# 4_cpu.net
KiCad netlist of a schematic drawn in Altium Designer
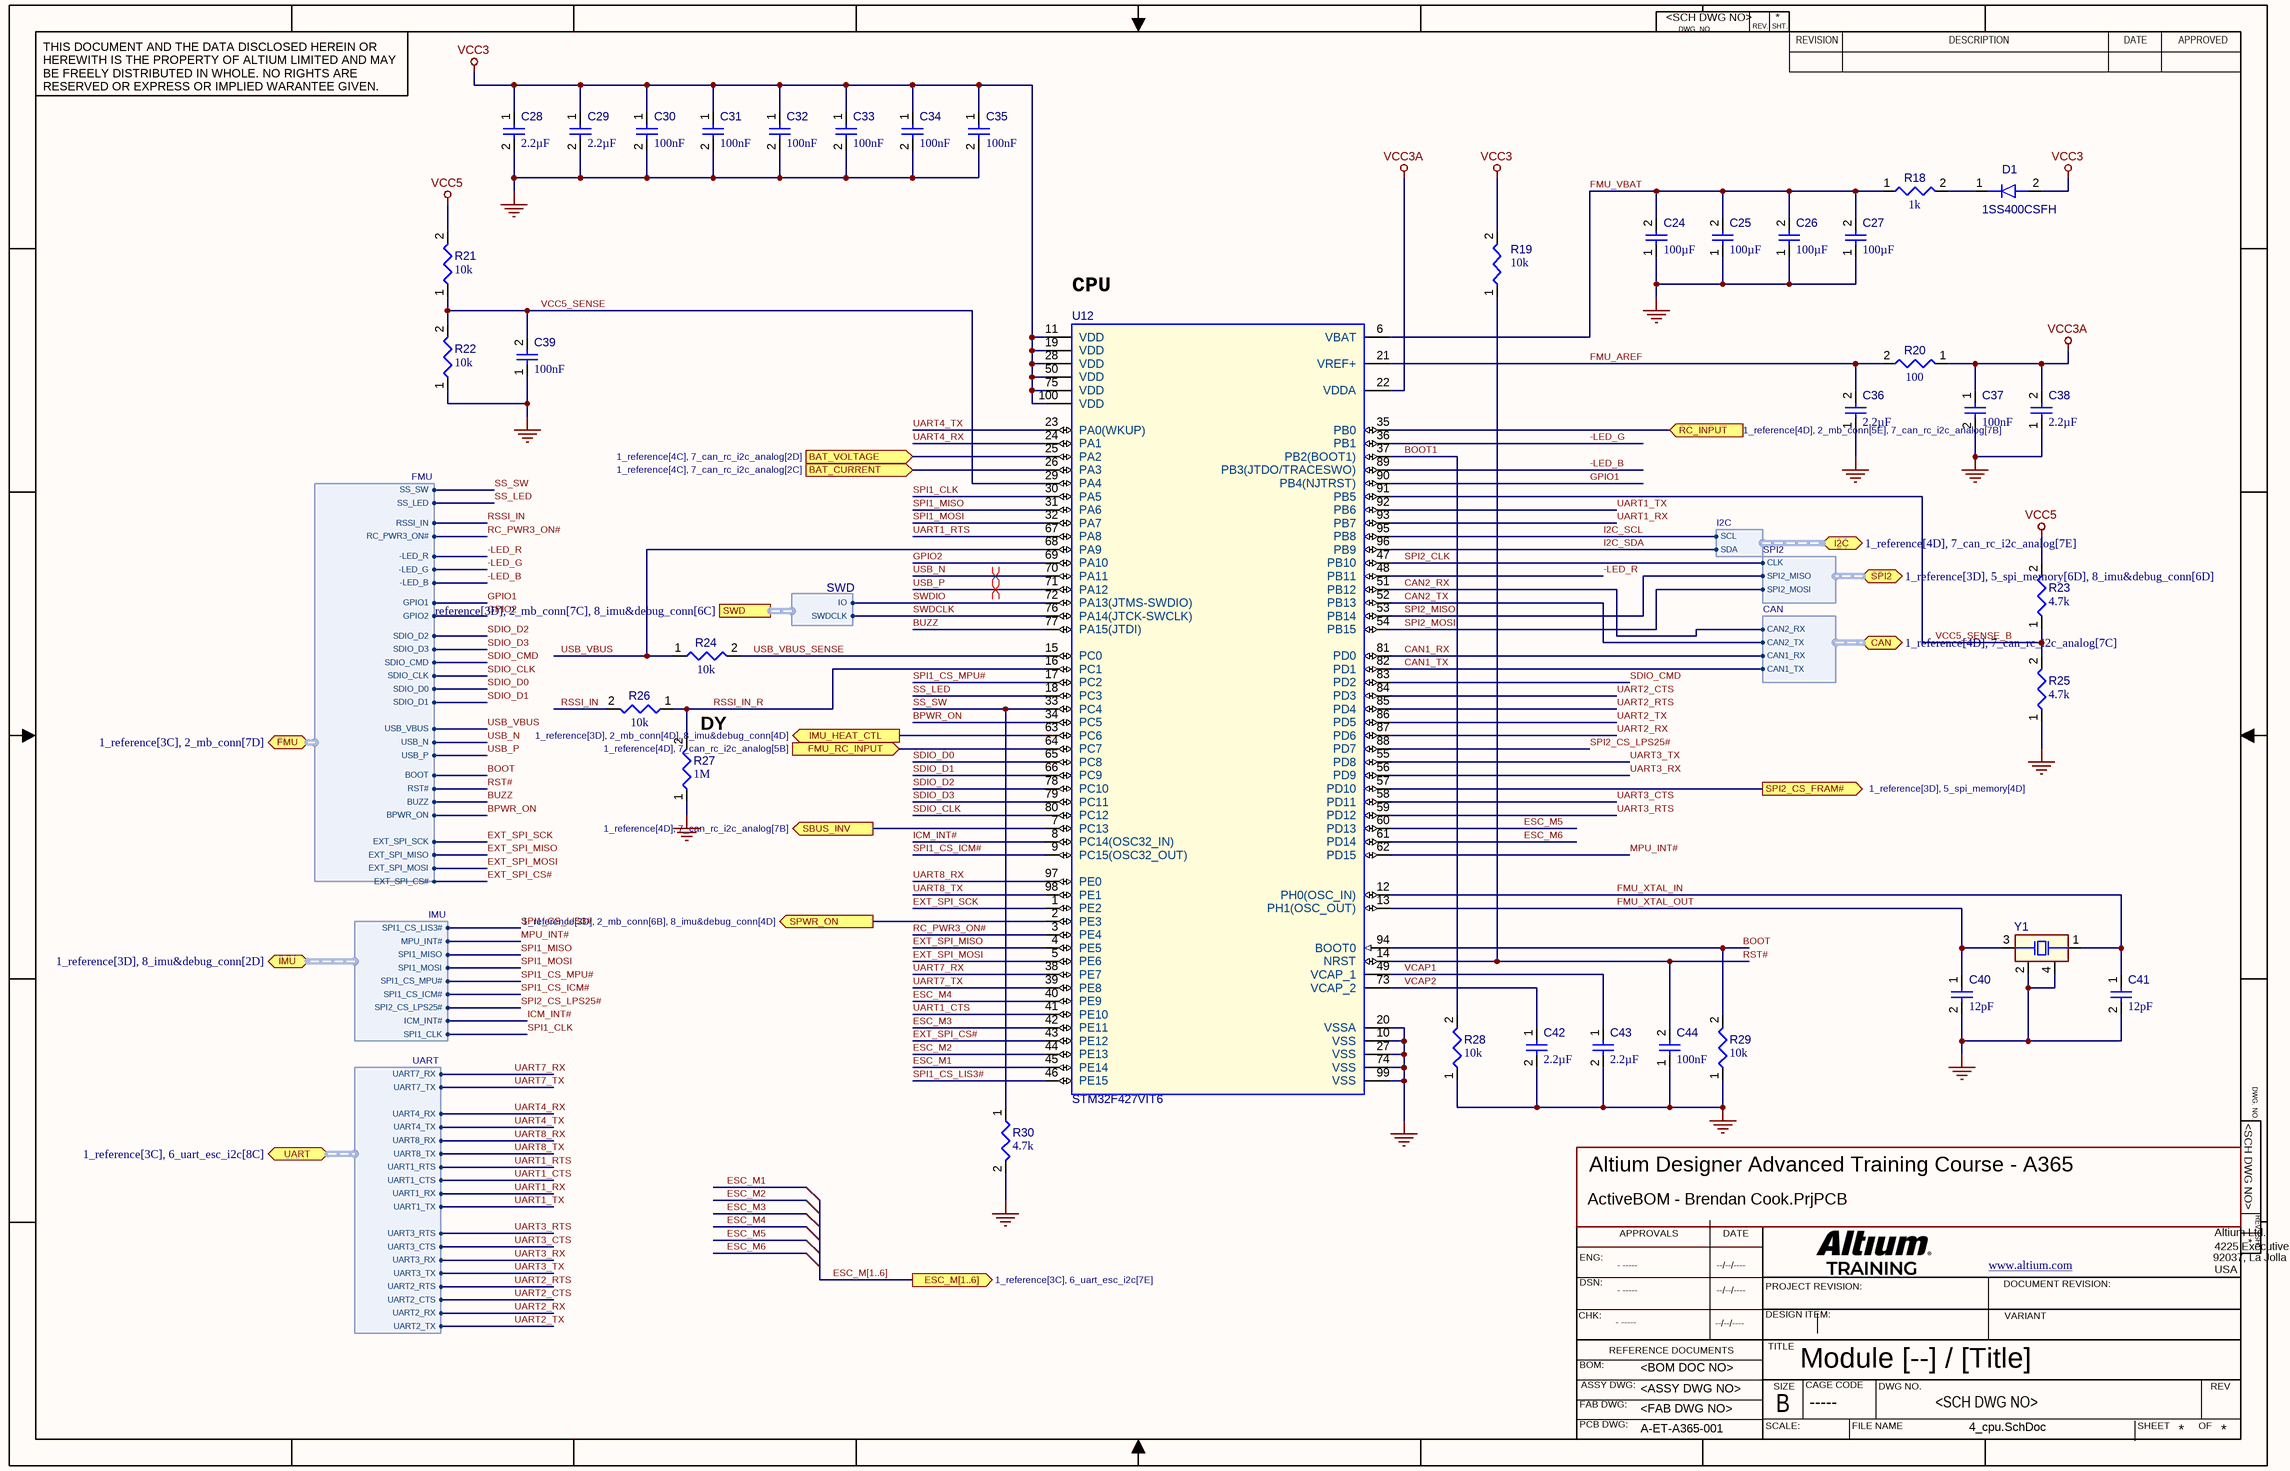
[diagram p0: 4_cpu.SchDoc]

(export (version "E")
  (design (tool "Eeschema 10.0.6"))
  (components
    (comp (ref "C24")
      (value "100µF")
      (footprint "CAPC0805(2012)145_L")
      (description "Chip Capacitor, 100µF +/-20%, 6.3V, 0805, Thickness 1.45 mm")
      (fields (field (name "TOLERANCE") "10%") (field (name "Comment") "Capacitor 100µF +/-20% 6.3V 0805"))
      (libsource (lib "MHH -  Altium Advanced Course A365 01") (part "CAP-NP-2"))
    )
    (comp (ref "C25")
      (value "100µF")
      (footprint "CAPC0805(2012)145_L")
      (description "Chip Capacitor, 100µF +/-20%, 6.3V, 0805, Thickness 1.45 mm")
      (fields (field (name "TOLERANCE") "10%") (field (name "Comment") "Capacitor 100µF +/-20% 6.3V 0805"))
      (libsource (lib "MHH -  Altium Advanced Course A365 01") (part "CAP-NP-2"))
    )
    (comp (ref "C26")
      (value "100µF")
      (footprint "CAPC0805(2012)145_L")
      (description "Chip Capacitor, 100µF +/-20%, 6.3V, 0805, Thickness 1.45 mm")
      (fields (field (name "TOLERANCE") "10%") (field (name "Comment") "Capacitor 100µF +/-20% 6.3V 0805"))
      (libsource (lib "MHH -  Altium Advanced Course A365 01") (part "CAP-NP-2"))
    )
    (comp (ref "C27")
      (value "100µF")
      (footprint "CAPC0805(2012)145_L")
      (description "Chip Capacitor, 100µF +/-20%, 6.3V, 0805, Thickness 1.45 mm")
      (fields (field (name "TOLERANCE") "10%") (field (name "Comment") "Capacitor 100µF +/-20% 6.3V 0805"))
      (libsource (lib "MHH -  Altium Advanced Course A365 01") (part "CAP-NP-2"))
    )
    (comp (ref "C28")
      (value "2.2µF")
      (footprint "CAPC0402(1005)60_L")
      (description "Chip Capacitor, 2,2µF +/-20%, 10V, 0402, Thickness 0.6 mm")
      (fields (field (name "TOLERANCE") "10%") (field (name "Comment") "Capacitor 2,2µF +/-20% 10V 0402"))
      (libsource (lib "MHH -  Altium Advanced Course A365 01") (part "CAP-NP-2"))
    )
    (comp (ref "C29")
      (value "2.2µF")
      (footprint "CAPC0402(1005)60_L")
      (description "Chip Capacitor, 2,2µF +/-20%, 10V, 0402, Thickness 0.6 mm")
      (fields (field (name "TOLERANCE") "10%") (field (name "Comment") "Capacitor 2,2µF +/-20% 10V 0402"))
      (libsource (lib "MHH -  Altium Advanced Course A365 01") (part "CAP-NP-2"))
    )
    (comp (ref "C30")
      (value "100nF")
      (footprint "CAPC0402(1005)60_L")
      (description "Chip Capacitor, 100nF +/-20%, 10V, 0402, Thickness 0.6 mm")
      (fields (field (name "TOLERANCE") "20%") (field (name "Comment") "Capacitor 100nF +/-20% 10V 0402"))
      (libsource (lib "MHH -  Altium Advanced Course A365 01") (part "CAP-NP-2"))
    )
    (comp (ref "C31")
      (value "100nF")
      (footprint "CAPC0402(1005)60_L")
      (description "Chip Capacitor, 100nF +/-20%, 10V, 0402, Thickness 0.6 mm")
      (fields (field (name "TOLERANCE") "20%") (field (name "Comment") "Capacitor 100nF +/-20% 10V 0402"))
      (libsource (lib "MHH -  Altium Advanced Course A365 01") (part "CAP-NP-2"))
    )
    (comp (ref "C32")
      (value "100nF")
      (footprint "CAPC0402(1005)60_L")
      (description "Chip Capacitor, 100nF +/-20%, 10V, 0402, Thickness 0.6 mm")
      (fields (field (name "TOLERANCE") "20%") (field (name "Comment") "Capacitor 100nF +/-20% 10V 0402"))
      (libsource (lib "MHH -  Altium Advanced Course A365 01") (part "CAP-NP-2"))
    )
    (comp (ref "C33")
      (value "100nF")
      (footprint "CAPC0402(1005)60_L")
      (description "Chip Capacitor, 100nF +/-20%, 10V, 0402, Thickness 0.6 mm")
      (fields (field (name "TOLERANCE") "20%") (field (name "Comment") "Capacitor 100nF +/-20% 10V 0402"))
      (libsource (lib "MHH -  Altium Advanced Course A365 01") (part "CAP-NP-2"))
    )
    (comp (ref "C34")
      (value "100nF")
      (footprint "CAPC0402(1005)60_L")
      (description "Chip Capacitor, 100nF +/-20%, 10V, 0402, Thickness 0.6 mm")
      (fields (field (name "TOLERANCE") "20%") (field (name "Comment") "Capacitor 100nF +/-20% 10V 0402"))
      (libsource (lib "MHH -  Altium Advanced Course A365 01") (part "CAP-NP-2"))
    )
    (comp (ref "C35")
      (value "100nF")
      (footprint "CAPC0402(1005)60_L")
      (description "Chip Capacitor, 100nF +/-20%, 10V, 0402, Thickness 0.6 mm")
      (fields (field (name "TOLERANCE") "20%") (field (name "Comment") "Capacitor 100nF +/-20% 10V 0402"))
      (libsource (lib "MHH -  Altium Advanced Course A365 01") (part "CAP-NP-2"))
    )
    (comp (ref "C36")
      (value "2.2µF")
      (footprint "CAPC0402(1005)60_L")
      (description "Chip Capacitor, 2,2µF +/-20%, 10V, 0402, Thickness 0.6 mm")
      (fields (field (name "TOLERANCE") "10%") (field (name "Comment") "Capacitor 2,2µF +/-20% 10V 0402"))
      (libsource (lib "MHH -  Altium Advanced Course A365 01") (part "CAP-NP-2"))
    )
    (comp (ref "C37")
      (value "100nF")
      (footprint "CAPC0402(1005)60_L")
      (description "Chip Capacitor, 100nF +/-20%, 10V, 0402, Thickness 0.6 mm")
      (fields (field (name "TOLERANCE") "20%") (field (name "Comment") "Capacitor 100nF +/-20% 10V 0402"))
      (libsource (lib "MHH -  Altium Advanced Course A365 01") (part "CAP-NP-2"))
    )
    (comp (ref "C38")
      (value "2.2µF")
      (footprint "CAPC0402(1005)60_L")
      (description "Chip Capacitor, 2,2µF +/-20%, 10V, 0402, Thickness 0.6 mm")
      (fields (field (name "TOLERANCE") "10%") (field (name "Comment") "Capacitor 2,2µF +/-20% 10V 0402"))
      (libsource (lib "MHH -  Altium Advanced Course A365 01") (part "CAP-NP-2"))
    )
    (comp (ref "C39")
      (value "100nF")
      (footprint "CAPC0402(1005)60_L")
      (description "Chip Capacitor, 100nF +/-20%, 10V, 0402, Thickness 0.6 mm")
      (fields (field (name "TOLERANCE") "20%") (field (name "Comment") "Capacitor 100nF +/-20% 10V 0402"))
      (libsource (lib "MHH -  Altium Advanced Course A365 01") (part "CAP-NP-2"))
    )
    (comp (ref "C40")
      (value "12pF")
      (footprint "CAPC0402(1005)33_L")
      (description "Chip Capacitor, 12pF +/-10%, 50V, 0402, Thickness 0.33 mm")
      (fields (field (name "TOLERANCE") "20%") (field (name "Comment") "Capacitor 12pF +/-10% 50V 0402"))
      (libsource (lib "MHH -  Altium Advanced Course A365 01") (part "CAP-NP-2"))
    )
    (comp (ref "C41")
      (value "12pF")
      (footprint "CAPC0402(1005)33_L")
      (description "Chip Capacitor, 12pF +/-10%, 50V, 0402, Thickness 0.33 mm")
      (fields (field (name "TOLERANCE") "20%") (field (name "Comment") "Capacitor 12pF +/-10% 50V 0402"))
      (libsource (lib "MHH -  Altium Advanced Course A365 01") (part "CAP-NP-2"))
    )
    (comp (ref "C42")
      (value "2.2µF")
      (footprint "CAPC0402(1005)60_L")
      (description "Chip Capacitor, 2,2µF +/-20%, 10V, 0402, Thickness 0.6 mm")
      (fields (field (name "TOLERANCE") "10%") (field (name "Comment") "Capacitor 2,2µF +/-20% 10V 0402"))
      (libsource (lib "MHH -  Altium Advanced Course A365 01") (part "CAP-NP-2"))
    )
    (comp (ref "C43")
      (value "2.2µF")
      (footprint "CAPC0402(1005)60_L")
      (description "Chip Capacitor, 2,2µF +/-20%, 10V, 0402, Thickness 0.6 mm")
      (fields (field (name "TOLERANCE") "10%") (field (name "Comment") "Capacitor 2,2µF +/-20% 10V 0402"))
      (libsource (lib "MHH -  Altium Advanced Course A365 01") (part "CAP-NP-2"))
    )
    (comp (ref "C44")
      (value "100nF")
      (footprint "CAPC0402(1005)60_L")
      (description "Chip Capacitor, 100nF +/-20%, 10V, 0402, Thickness 0.6 mm")
      (fields (field (name "TOLERANCE") "20%") (field (name "Comment") "Capacitor 100nF +/-20% 10V 0402"))
      (libsource (lib "MHH -  Altium Advanced Course A365 01") (part "CAP-NP-2"))
    )
    (comp (ref "D1")
      (value "1SS400CSFH")
      (footprint "ROHM-VMN2-2_V")
      (description "Switching Diode (High Speed Switching), 80 V, 100 mA, 2-Pin SOD-923, RoHS, Tape and Reel")
      (libsource (lib "MHH -  Altium Advanced Course A365 01") (part "D-KA-2"))
    )
    (comp (ref "R18")
      (value "1k")
      (footprint "RESC0402(1005)_L")
      (description "Chip Resistor, 1 kOhms, +/-5 %, 63 mW, -55 to 155 degC, 0402")
      (fields (field (name "TOLERANCE") "5%") (field (name "POWER") "63mW"))
      (libsource (lib "MHH -  Altium Advanced Course A365 01") (part "RES-2"))
    )
    (comp (ref "R19")
      (value "10k")
      (footprint "RESC0402(1005)_L")
      (description "Chip Resistor, 10 kOhms, +/-1 %, 63 mW, -55 to 125 degC, 0402")
      (fields (field (name "TOLERANCE") "1%") (field (name "POWER") "63mW"))
      (libsource (lib "MHH -  Altium Advanced Course A365 01") (part "RES-2"))
    )
    (comp (ref "R20")
      (value "100")
      (footprint "RESC0402(1005)_L")
      (description "Chip Resistor, 100 Ohms, +/-1 %, 63 mW, -55 to 155 degC, 0402")
      (fields (field (name "TOLERANCE") "1%") (field (name "POWER") "63mW"))
      (libsource (lib "MHH -  Altium Advanced Course A365 01") (part "RES-2"))
    )
    (comp (ref "R21")
      (value "10k")
      (footprint "RESC0402(1005)_L")
      (description "Chip Resistor, 10 kOhms, +/-1 %, 63 mW, -55 to 125 degC, 0402")
      (fields (field (name "TOLERANCE") "1%") (field (name "POWER") "63mW"))
      (libsource (lib "MHH -  Altium Advanced Course A365 01") (part "RES-2"))
    )
    (comp (ref "R22")
      (value "10k")
      (footprint "RESC0402(1005)_L")
      (description "Chip Resistor, 10 kOhms, +/-1 %, 63 mW, -55 to 125 degC, 0402")
      (fields (field (name "TOLERANCE") "1%") (field (name "POWER") "63mW"))
      (libsource (lib "MHH -  Altium Advanced Course A365 01") (part "RES-2"))
    )
    (comp (ref "R23")
      (value "4.7k")
      (footprint "RESC0402(1005)_L")
      (description "Chip Resistor, 4,7 kOhms, +/-1 %, 63 mW, -55 to 155 degC, 0402")
      (fields (field (name "TOLERANCE") "1%") (field (name "POWER") "63mW"))
      (libsource (lib "MHH -  Altium Advanced Course A365 01") (part "RES-2"))
    )
    (comp (ref "R24")
      (value "10k")
      (footprint "RESC0402(1005)_L")
      (description "Chip Resistor, 10 kOhms, +/-1 %, 63 mW, -55 to 125 degC, 0402")
      (fields (field (name "TOLERANCE") "1%") (field (name "POWER") "63mW"))
      (libsource (lib "MHH -  Altium Advanced Course A365 01") (part "RES-2"))
    )
    (comp (ref "R25")
      (value "4.7k")
      (footprint "RESC0402(1005)_L")
      (description "Chip Resistor, 4,7 kOhms, +/-1 %, 63 mW, -55 to 155 degC, 0402")
      (fields (field (name "TOLERANCE") "1%") (field (name "POWER") "63mW"))
      (libsource (lib "MHH -  Altium Advanced Course A365 01") (part "RES-2"))
    )
    (comp (ref "R26")
      (value "10k")
      (footprint "RESC0402(1005)_L")
      (description "Chip Resistor, 10 kOhms, +/-1 %, 63 mW, -55 to 125 degC, 0402")
      (fields (field (name "TOLERANCE") "1%") (field (name "POWER") "63mW"))
      (libsource (lib "MHH -  Altium Advanced Course A365 01") (part "RES-2"))
    )
    (comp (ref "R27")
      (value "1M")
      (footprint "RESC0402(1005)_L")
      (description "Chip Resistor, 1 MOhms, +/-5 %, 63 mW, -55 to 155 degC, 0402")
      (fields (field (name "TOLERANCE") "5%") (field (name "POWER") "63mW"))
      (libsource (lib "MHH -  Altium Advanced Course A365 01") (part "RES-2"))
    )
    (comp (ref "R28")
      (value "10k")
      (footprint "RESC0402(1005)_L")
      (description "Chip Resistor, 10 kOhms, +/-1 %, 63 mW, -55 to 125 degC, 0402")
      (fields (field (name "TOLERANCE") "1%") (field (name "POWER") "63mW"))
      (libsource (lib "MHH -  Altium Advanced Course A365 01") (part "RES-2"))
    )
    (comp (ref "R29")
      (value "10k")
      (footprint "RESC0402(1005)_L")
      (description "Chip Resistor, 10 kOhms, +/-1 %, 63 mW, -55 to 125 degC, 0402")
      (fields (field (name "TOLERANCE") "1%") (field (name "POWER") "63mW"))
      (libsource (lib "MHH -  Altium Advanced Course A365 01") (part "RES-2"))
    )
    (comp (ref "R30")
      (value "4.7k")
      (footprint "RESC0402(1005)_L")
      (description "Chip Resistor, 4,7 kOhms, +/-1 %, 63 mW, -55 to 155 degC, 0402")
      (fields (field (name "TOLERANCE") "1%") (field (name "POWER") "63mW"))
      (libsource (lib "MHH -  Altium Advanced Course A365 01") (part "RES-2"))
    )
    (comp (ref "U12")
      (value "STM32F427VIT6")
      (footprint "STM-LQFP100")
      (libsource (lib "MHH -  Altium Advanced Course A365 01") (part "CMP-00125-5"))
    )
    (comp (ref "Y1")
      (value "FA-12824.0000MF10Z-W3")
      (footprint "EPSON-FA-128_V")
      (description "Crystal, 24 MHz, +/- 10 ppm, -20 to 75 degC, 4-Pin SMD, RoHS, Tape and Reel")
      (libsource (lib "MHH -  Altium Advanced Course A365 01") (part "CMP-00014-7"))
    )
  )
  (nets
    (net (code "8") (name "/-LED_B") (class "Default")
      (node (ref "U12") (pin "89") (pinfunction "PB3(JTDO/TRACESWO)_89") (pintype "bidirectional"))
    )
    (net (code "9") (name "/-LED_G") (class "Default")
      (node (ref "U12") (pin "36") (pinfunction "PB1_36") (pintype "bidirectional"))
    )
    (net (code "10") (name "/-LED_R") (class "Default")
      (node (ref "U12") (pin "48") (pinfunction "PB11_48") (pintype "bidirectional"))
    )
    (net (code "11") (name "/BAT_CURRENT") (class "Default")
      (node (ref "U12") (pin "26") (pinfunction "PA3_26") (pintype "bidirectional"))
    )
    (net (code "12") (name "/BAT_VOLTAGE") (class "Default")
      (node (ref "U12") (pin "25") (pinfunction "PA2_25") (pintype "bidirectional"))
    )
    (net (code "13") (name "/BOOT") (class "Default")
      (node (ref "R29") (pin "2") (pinfunction "2_2") (pintype "passive"))
      (node (ref "U12") (pin "94") (pinfunction "BOOT0_94") (pintype "input"))
    )
    (net (code "14") (name "/BOOT1") (class "Default")
      (node (ref "R28") (pin "2") (pinfunction "2_2") (pintype "passive"))
      (node (ref "U12") (pin "37") (pinfunction "PB2(BOOT1)_37") (pintype "bidirectional"))
    )
    (net (code "15") (name "/BPWR_ON") (class "Default")
      (node (ref "U12") (pin "34") (pinfunction "PC5_34") (pintype "bidirectional"))
    )
    (net (code "16") (name "/BUZZ") (class "Default")
      (node (ref "U12") (pin "77") (pinfunction "PA15(JTDI)_77") (pintype "bidirectional"))
    )
    (net (code "17") (name "/CAN1_RX") (class "Default")
      (node (ref "U12") (pin "81") (pinfunction "PD0_81") (pintype "bidirectional"))
    )
    (net (code "18") (name "/CAN1_TX") (class "Default")
      (node (ref "U12") (pin "82") (pinfunction "PD1_82") (pintype "bidirectional"))
    )
    (net (code "19") (name "/CAN2_RX") (class "Default")
      (node (ref "U12") (pin "51") (pinfunction "PB12_51") (pintype "bidirectional"))
    )
    (net (code "20") (name "/CAN2_TX") (class "Default")
      (node (ref "U12") (pin "52") (pinfunction "PB13_52") (pintype "bidirectional"))
    )
    (net (code "21") (name "/ESC_M1") (class "Default")
      (node (ref "U12") (pin "45") (pinfunction "PE14_45") (pintype "bidirectional"))
    )
    (net (code "22") (name "/ESC_M2") (class "Default")
      (node (ref "U12") (pin "44") (pinfunction "PE13_44") (pintype "bidirectional"))
    )
    (net (code "23") (name "/ESC_M3") (class "Default")
      (node (ref "U12") (pin "42") (pinfunction "PE11_42") (pintype "bidirectional"))
    )
    (net (code "24") (name "/ESC_M4") (class "Default")
      (node (ref "U12") (pin "40") (pinfunction "PE9_40") (pintype "bidirectional"))
    )
    (net (code "25") (name "/ESC_M5") (class "Default")
      (node (ref "U12") (pin "60") (pinfunction "PD13_60") (pintype "bidirectional"))
    )
    (net (code "26") (name "/ESC_M6") (class "Default")
      (node (ref "U12") (pin "61") (pinfunction "PD14_61") (pintype "bidirectional"))
    )
    (net (code "28") (name "/EXT_SPI_CS#") (class "Default")
      (node (ref "U12") (pin "43") (pinfunction "PE12_43") (pintype "bidirectional"))
    )
    (net (code "29") (name "/EXT_SPI_MISO") (class "Default")
      (node (ref "U12") (pin "4") (pinfunction "PE5_4") (pintype "bidirectional"))
    )
    (net (code "30") (name "/EXT_SPI_MOSI") (class "Default")
      (node (ref "U12") (pin "5") (pinfunction "PE6_5") (pintype "bidirectional"))
    )
    (net (code "31") (name "/EXT_SPI_SCK") (class "Default")
      (node (ref "U12") (pin "1") (pinfunction "PE2_1") (pintype "bidirectional"))
    )
    (net (code "32") (name "/FMU_AREF") (class "Default")
      (node (ref "C36") (pin "2") (pinfunction "2_2") (pintype "passive"))
      (node (ref "R20") (pin "2") (pinfunction "2_2") (pintype "passive"))
      (node (ref "U12") (pin "21") (pinfunction "VREF+_21") (pintype "power_in"))
    )
    (net (code "33") (name "/FMU_RC_INPUT") (class "Default")
      (node (ref "U12") (pin "64") (pinfunction "PC7_64") (pintype "bidirectional"))
    )
    (net (code "34") (name "/FMU_VBAT") (class "Default")
      (node (ref "C24") (pin "2") (pinfunction "2_2") (pintype "passive"))
      (node (ref "C25") (pin "2") (pinfunction "2_2") (pintype "passive"))
      (node (ref "C26") (pin "2") (pinfunction "2_2") (pintype "passive"))
      (node (ref "C27") (pin "2") (pinfunction "2_2") (pintype "passive"))
      (node (ref "R18") (pin "1") (pinfunction "1_1") (pintype "passive"))
      (node (ref "U12") (pin "6") (pinfunction "VBAT_6") (pintype "power_in"))
    )
    (net (code "35") (name "/FMU_XTAL_IN") (class "Default")
      (node (ref "C41") (pin "1") (pinfunction "1_1") (pintype "passive"))
      (node (ref "U12") (pin "12") (pinfunction "PH0(OSC_IN)_12") (pintype "bidirectional"))
      (node (ref "Y1") (pin "1") (pinfunction "X1_1") (pintype "passive"))
    )
    (net (code "36") (name "/FMU_XTAL_OUT") (class "Default")
      (node (ref "C40") (pin "1") (pinfunction "1_1") (pintype "passive"))
      (node (ref "U12") (pin "13") (pinfunction "PH1(OSC_OUT)_13") (pintype "bidirectional"))
      (node (ref "Y1") (pin "3") (pinfunction "X2_3") (pintype "passive"))
    )
    (net (code "37") (name "/GPIO1") (class "Default")
      (node (ref "U12") (pin "90") (pinfunction "PB4(NJTRST)_90") (pintype "bidirectional"))
    )
    (net (code "38") (name "/GPIO2") (class "Default")
      (node (ref "U12") (pin "69") (pinfunction "PA10_69") (pintype "bidirectional"))
    )
    (net (code "39") (name "/I2C_SCL") (class "Default")
      (node (ref "U12") (pin "95") (pinfunction "PB8_95") (pintype "bidirectional"))
    )
    (net (code "40") (name "/I2C_SDA") (class "Default")
      (node (ref "U12") (pin "96") (pinfunction "PB9_96") (pintype "bidirectional"))
    )
    (net (code "41") (name "/ICM_INT#") (class "Default")
      (node (ref "U12") (pin "8") (pinfunction "PC14(OSC32_IN)_8") (pintype "bidirectional"))
    )
    (net (code "42") (name "/IMU_HEAT_CTL") (class "Default")
      (node (ref "U12") (pin "63") (pinfunction "PC6_63") (pintype "bidirectional"))
    )
    (net (code "43") (name "/MPU_INT#") (class "Default")
      (node (ref "U12") (pin "62") (pinfunction "PD15_62") (pintype "bidirectional"))
    )
    (net (code "44") (name "/RC_INPUT") (class "Default")
      (node (ref "U12") (pin "35") (pinfunction "PB0_35") (pintype "bidirectional"))
    )
    (net (code "45") (name "/RC_PWR3_ON#") (class "Default")
      (node (ref "U12") (pin "3") (pinfunction "PE4_3") (pintype "bidirectional"))
    )
    (net (code "46") (name "/RSSI_IN") (class "Default")
      (node (ref "R26") (pin "2") (pinfunction "2_2") (pintype "passive"))
    )
    (net (code "47") (name "/RSSI_IN_R") (class "Default")
      (node (ref "R26") (pin "1") (pinfunction "1_1") (pintype "passive"))
      (node (ref "R27") (pin "2") (pinfunction "2_2") (pintype "passive"))
      (node (ref "U12") (pin "16") (pinfunction "PC1_16") (pintype "bidirectional"))
    )
    (net (code "48") (name "/RST#") (class "Default")
      (node (ref "C44") (pin "2") (pinfunction "2_2") (pintype "passive"))
      (node (ref "R19") (pin "1") (pinfunction "1_1") (pintype "passive"))
      (node (ref "U12") (pin "14") (pinfunction "NRST_14") (pintype "bidirectional"))
    )
    (net (code "49") (name "/SBUS_INV") (class "Default")
      (node (ref "U12") (pin "7") (pinfunction "PC13_7") (pintype "bidirectional"))
    )
    (net (code "50") (name "/SDIO_CLK") (class "Default")
      (node (ref "U12") (pin "80") (pinfunction "PC12_80") (pintype "bidirectional"))
    )
    (net (code "51") (name "/SDIO_CMD") (class "Default")
      (node (ref "U12") (pin "83") (pinfunction "PD2_83") (pintype "bidirectional"))
    )
    (net (code "52") (name "/SDIO_D0") (class "Default")
      (node (ref "U12") (pin "65") (pinfunction "PC8_65") (pintype "bidirectional"))
    )
    (net (code "53") (name "/SDIO_D1") (class "Default")
      (node (ref "U12") (pin "66") (pinfunction "PC9_66") (pintype "bidirectional"))
    )
    (net (code "54") (name "/SDIO_D2") (class "Default")
      (node (ref "U12") (pin "78") (pinfunction "PC10_78") (pintype "bidirectional"))
    )
    (net (code "55") (name "/SDIO_D3") (class "Default")
      (node (ref "U12") (pin "79") (pinfunction "PC11_79") (pintype "bidirectional"))
    )
    (net (code "56") (name "/SPI1_CLK") (class "Default")
      (node (ref "U12") (pin "30") (pinfunction "PA5_30") (pintype "bidirectional"))
    )
    (net (code "57") (name "/SPI1_CS_ICM#") (class "Default")
      (node (ref "U12") (pin "9") (pinfunction "PC15(OSC32_OUT)_9") (pintype "bidirectional"))
    )
    (net (code "58") (name "/SPI1_CS_LIS3#") (class "Default")
      (node (ref "U12") (pin "46") (pinfunction "PE15_46") (pintype "bidirectional"))
    )
    (net (code "59") (name "/SPI1_CS_MPU#") (class "Default")
      (node (ref "U12") (pin "17") (pinfunction "PC2_17") (pintype "bidirectional"))
    )
    (net (code "60") (name "/SPI1_MISO") (class "Default")
      (node (ref "U12") (pin "31") (pinfunction "PA6_31") (pintype "bidirectional"))
    )
    (net (code "61") (name "/SPI1_MOSI") (class "Default")
      (node (ref "U12") (pin "32") (pinfunction "PA7_32") (pintype "bidirectional"))
    )
    (net (code "62") (name "/SPI2_CLK") (class "Default")
      (node (ref "U12") (pin "47") (pinfunction "PB10_47") (pintype "bidirectional"))
    )
    (net (code "63") (name "/SPI2_CS_FRAM#") (class "Default")
      (node (ref "U12") (pin "57") (pinfunction "PD10_57") (pintype "bidirectional"))
    )
    (net (code "64") (name "/SPI2_CS_LPS25#") (class "Default")
      (node (ref "U12") (pin "88") (pinfunction "PD7_88") (pintype "bidirectional"))
    )
    (net (code "65") (name "/SPI2_MISO") (class "Default")
      (node (ref "U12") (pin "53") (pinfunction "PB14_53") (pintype "bidirectional"))
    )
    (net (code "66") (name "/SPI2_MOSI") (class "Default")
      (node (ref "U12") (pin "54") (pinfunction "PB15_54") (pintype "bidirectional"))
    )
    (net (code "67") (name "/SPWR_ON") (class "Default")
      (node (ref "U12") (pin "2") (pinfunction "PE3_2") (pintype "bidirectional"))
    )
    (net (code "68") (name "/SS_LED") (class "Default")
      (node (ref "U12") (pin "18") (pinfunction "PC3_18") (pintype "bidirectional"))
    )
    (net (code "69") (name "/SS_SW") (class "Default")
      (node (ref "R30") (pin "1") (pinfunction "1_1") (pintype "passive"))
      (node (ref "U12") (pin "33") (pinfunction "PC4_33") (pintype "bidirectional"))
    )
    (net (code "70") (name "/SWDCLK") (class "Default")
      (node (ref "U12") (pin "76") (pinfunction "PA14(JTCK-SWCLK)_76") (pintype "bidirectional"))
    )
    (net (code "71") (name "/SWDIO") (class "Default")
      (node (ref "U12") (pin "72") (pinfunction "PA13(JTMS-SWDIO)_72") (pintype "bidirectional"))
    )
    (net (code "72") (name "/UART1_CTS") (class "Default")
      (node (ref "U12") (pin "41") (pinfunction "PE10_41") (pintype "bidirectional"))
    )
    (net (code "73") (name "/UART1_RTS") (class "Default")
      (node (ref "U12") (pin "67") (pinfunction "PA8_67") (pintype "bidirectional"))
    )
    (net (code "74") (name "/UART1_RX") (class "Default")
      (node (ref "U12") (pin "93") (pinfunction "PB7_93") (pintype "bidirectional"))
    )
    (net (code "75") (name "/UART1_TX") (class "Default")
      (node (ref "U12") (pin "92") (pinfunction "PB6_92") (pintype "bidirectional"))
    )
    (net (code "76") (name "/UART2_CTS") (class "Default")
      (node (ref "U12") (pin "84") (pinfunction "PD3_84") (pintype "bidirectional"))
    )
    (net (code "77") (name "/UART2_RTS") (class "Default")
      (node (ref "U12") (pin "85") (pinfunction "PD4_85") (pintype "bidirectional"))
    )
    (net (code "78") (name "/UART2_RX") (class "Default")
      (node (ref "U12") (pin "87") (pinfunction "PD6_87") (pintype "bidirectional"))
    )
    (net (code "79") (name "/UART2_TX") (class "Default")
      (node (ref "U12") (pin "86") (pinfunction "PD5_86") (pintype "bidirectional"))
    )
    (net (code "80") (name "/UART3_CTS") (class "Default")
      (node (ref "U12") (pin "58") (pinfunction "PD11_58") (pintype "bidirectional"))
    )
    (net (code "81") (name "/UART3_RTS") (class "Default")
      (node (ref "U12") (pin "59") (pinfunction "PD12_59") (pintype "bidirectional"))
    )
    (net (code "82") (name "/UART3_RX") (class "Default")
      (node (ref "U12") (pin "56") (pinfunction "PD9_56") (pintype "bidirectional"))
    )
    (net (code "83") (name "/UART3_TX") (class "Default")
      (node (ref "U12") (pin "55") (pinfunction "PD8_55") (pintype "bidirectional"))
    )
    (net (code "84") (name "/UART4_RX") (class "Default")
      (node (ref "U12") (pin "24") (pinfunction "PA1_24") (pintype "bidirectional"))
    )
    (net (code "85") (name "/UART4_TX") (class "Default")
      (node (ref "U12") (pin "23") (pinfunction "PA0(WKUP)_23") (pintype "bidirectional"))
    )
    (net (code "86") (name "/UART7_RX") (class "Default")
      (node (ref "U12") (pin "38") (pinfunction "PE7_38") (pintype "bidirectional"))
    )
    (net (code "87") (name "/UART7_TX") (class "Default")
      (node (ref "U12") (pin "39") (pinfunction "PE8_39") (pintype "bidirectional"))
    )
    (net (code "88") (name "/UART8_RX") (class "Default")
      (node (ref "U12") (pin "97") (pinfunction "PE0_97") (pintype "bidirectional"))
    )
    (net (code "89") (name "/UART8_TX") (class "Default")
      (node (ref "U12") (pin "98") (pinfunction "PE1_98") (pintype "bidirectional"))
    )
    (net (code "90") (name "/USB_N") (class "Default")
      (node (ref "U12") (pin "70") (pinfunction "PA11_70") (pintype "bidirectional"))
    )
    (net (code "91") (name "/USB_P") (class "Default")
      (node (ref "U12") (pin "71") (pinfunction "PA12_71") (pintype "bidirectional"))
    )
    (net (code "92") (name "/USB_VBUS") (class "Default")
      (node (ref "R24") (pin "1") (pinfunction "1_1") (pintype "passive"))
      (node (ref "U12") (pin "68") (pinfunction "PA9_68") (pintype "bidirectional"))
    )
    (net (code "93") (name "/USB_VBUS_SENSE") (class "Default")
      (node (ref "R24") (pin "2") (pinfunction "2_2") (pintype "passive"))
      (node (ref "U12") (pin "15") (pinfunction "PC0_15") (pintype "bidirectional"))
    )
    (net (code "94") (name "/VCAP1") (class "Default")
      (node (ref "C43") (pin "1") (pinfunction "1_1") (pintype "passive"))
      (node (ref "U12") (pin "49") (pinfunction "VCAP_1_49") (pintype "passive"))
    )
    (net (code "95") (name "/VCAP2") (class "Default")
      (node (ref "C42") (pin "1") (pinfunction "1_1") (pintype "passive"))
      (node (ref "U12") (pin "73") (pinfunction "VCAP_2_73") (pintype "passive"))
    )
    (net (code "96") (name "/VCC5_SENSE") (class "Default")
      (node (ref "C39") (pin "2") (pinfunction "2_2") (pintype "passive"))
      (node (ref "R21") (pin "1") (pinfunction "1_1") (pintype "passive"))
      (node (ref "R22") (pin "2") (pinfunction "2_2") (pintype "passive"))
      (node (ref "U12") (pin "29") (pinfunction "PA4_29") (pintype "bidirectional"))
    )
    (net (code "97") (name "/VCC5_SENSE_B") (class "Default")
      (node (ref "R23") (pin "1") (pinfunction "1_1") (pintype "passive"))
      (node (ref "R25") (pin "2") (pinfunction "2_2") (pintype "passive"))
      (node (ref "U12") (pin "91") (pinfunction "PB5_91") (pintype "bidirectional"))
    )
    (net (code "105") (name "GND") (class "Default")
      (node (ref "C24") (pin "1") (pinfunction "1_1") (pintype "passive"))
      (node (ref "C25") (pin "1") (pinfunction "1_1") (pintype "passive"))
      (node (ref "C26") (pin "1") (pinfunction "1_1") (pintype "passive"))
      (node (ref "C27") (pin "1") (pinfunction "1_1") (pintype "passive"))
      (node (ref "C28") (pin "2") (pinfunction "2_2") (pintype "passive"))
      (node (ref "C29") (pin "2") (pinfunction "2_2") (pintype "passive"))
      (node (ref "C30") (pin "2") (pinfunction "2_2") (pintype "passive"))
      (node (ref "C31") (pin "2") (pinfunction "2_2") (pintype "passive"))
      (node (ref "C32") (pin "2") (pinfunction "2_2") (pintype "passive"))
      (node (ref "C33") (pin "2") (pinfunction "2_2") (pintype "passive"))
      (node (ref "C34") (pin "2") (pinfunction "2_2") (pintype "passive"))
      (node (ref "C35") (pin "2") (pinfunction "2_2") (pintype "passive"))
      (node (ref "C36") (pin "1") (pinfunction "1_1") (pintype "passive"))
      (node (ref "C37") (pin "2") (pinfunction "2_2") (pintype "passive"))
      (node (ref "C38") (pin "1") (pinfunction "1_1") (pintype "passive"))
      (node (ref "C39") (pin "1") (pinfunction "1_1") (pintype "passive"))
      (node (ref "C40") (pin "2") (pinfunction "2_2") (pintype "passive"))
      (node (ref "C41") (pin "2") (pinfunction "2_2") (pintype "passive"))
      (node (ref "C42") (pin "2") (pinfunction "2_2") (pintype "passive"))
      (node (ref "C43") (pin "2") (pinfunction "2_2") (pintype "passive"))
      (node (ref "C44") (pin "1") (pinfunction "1_1") (pintype "passive"))
      (node (ref "R22") (pin "1") (pinfunction "1_1") (pintype "passive"))
      (node (ref "R25") (pin "1") (pinfunction "1_1") (pintype "passive"))
      (node (ref "R27") (pin "1") (pinfunction "1_1") (pintype "passive"))
      (node (ref "R28") (pin "1") (pinfunction "1_1") (pintype "passive"))
      (node (ref "R29") (pin "1") (pinfunction "1_1") (pintype "passive"))
      (node (ref "R30") (pin "2") (pinfunction "2_2") (pintype "passive"))
      (node (ref "U12") (pin "10") (pinfunction "VSS_10") (pintype "power_in"))
      (node (ref "U12") (pin "20") (pinfunction "VSSA_20") (pintype "power_in"))
      (node (ref "U12") (pin "27") (pinfunction "VSS_27") (pintype "power_in"))
      (node (ref "U12") (pin "74") (pinfunction "VSS_74") (pintype "power_in"))
      (node (ref "U12") (pin "99") (pinfunction "VSS_99") (pintype "power_in"))
      (node (ref "Y1") (pin "2") (pinfunction "NC_2") (pintype "power_in"))
      (node (ref "Y1") (pin "4") (pinfunction "NC_4") (pintype "power_in"))
    )
    (net (code "106") (name "Net-(D1-K)") (class "Default")
      (node (ref "D1") (pin "1") (pinfunction "K_1") (pintype "passive"))
      (node (ref "R18") (pin "2") (pinfunction "2_2") (pintype "passive"))
    )
    (net (code "107") (name "VCC3") (class "Default")
      (node (ref "C28") (pin "1") (pinfunction "1_1") (pintype "passive"))
      (node (ref "C29") (pin "1") (pinfunction "1_1") (pintype "passive"))
      (node (ref "C30") (pin "1") (pinfunction "1_1") (pintype "passive"))
      (node (ref "C31") (pin "1") (pinfunction "1_1") (pintype "passive"))
      (node (ref "C32") (pin "1") (pinfunction "1_1") (pintype "passive"))
      (node (ref "C33") (pin "1") (pinfunction "1_1") (pintype "passive"))
      (node (ref "C34") (pin "1") (pinfunction "1_1") (pintype "passive"))
      (node (ref "C35") (pin "1") (pinfunction "1_1") (pintype "passive"))
      (node (ref "D1") (pin "2") (pinfunction "A_2") (pintype "passive"))
      (node (ref "R19") (pin "2") (pinfunction "2_2") (pintype "passive"))
      (node (ref "U12") (pin "100") (pinfunction "VDD_100") (pintype "power_in"))
      (node (ref "U12") (pin "11") (pinfunction "VDD_11") (pintype "power_in"))
      (node (ref "U12") (pin "19") (pinfunction "VDD_19") (pintype "power_in"))
      (node (ref "U12") (pin "28") (pinfunction "VDD_28") (pintype "power_in"))
      (node (ref "U12") (pin "50") (pinfunction "VDD_50") (pintype "power_in"))
      (node (ref "U12") (pin "75") (pinfunction "VDD_75") (pintype "power_in"))
    )
    (net (code "108") (name "VCC3A") (class "Default")
      (node (ref "C37") (pin "1") (pinfunction "1_1") (pintype "passive"))
      (node (ref "C38") (pin "2") (pinfunction "2_2") (pintype "passive"))
      (node (ref "R20") (pin "1") (pinfunction "1_1") (pintype "passive"))
      (node (ref "U12") (pin "22") (pinfunction "VDDA_22") (pintype "power_in"))
    )
    (net (code "109") (name "VCC5") (class "Default")
      (node (ref "R21") (pin "2") (pinfunction "2_2") (pintype "passive"))
      (node (ref "R23") (pin "2") (pinfunction "2_2") (pintype "passive"))
    )
  )
)
